# Qwiic_Power_Meter-ACS37800.net
KiCad netlist of a schematic drawn in EAGLE
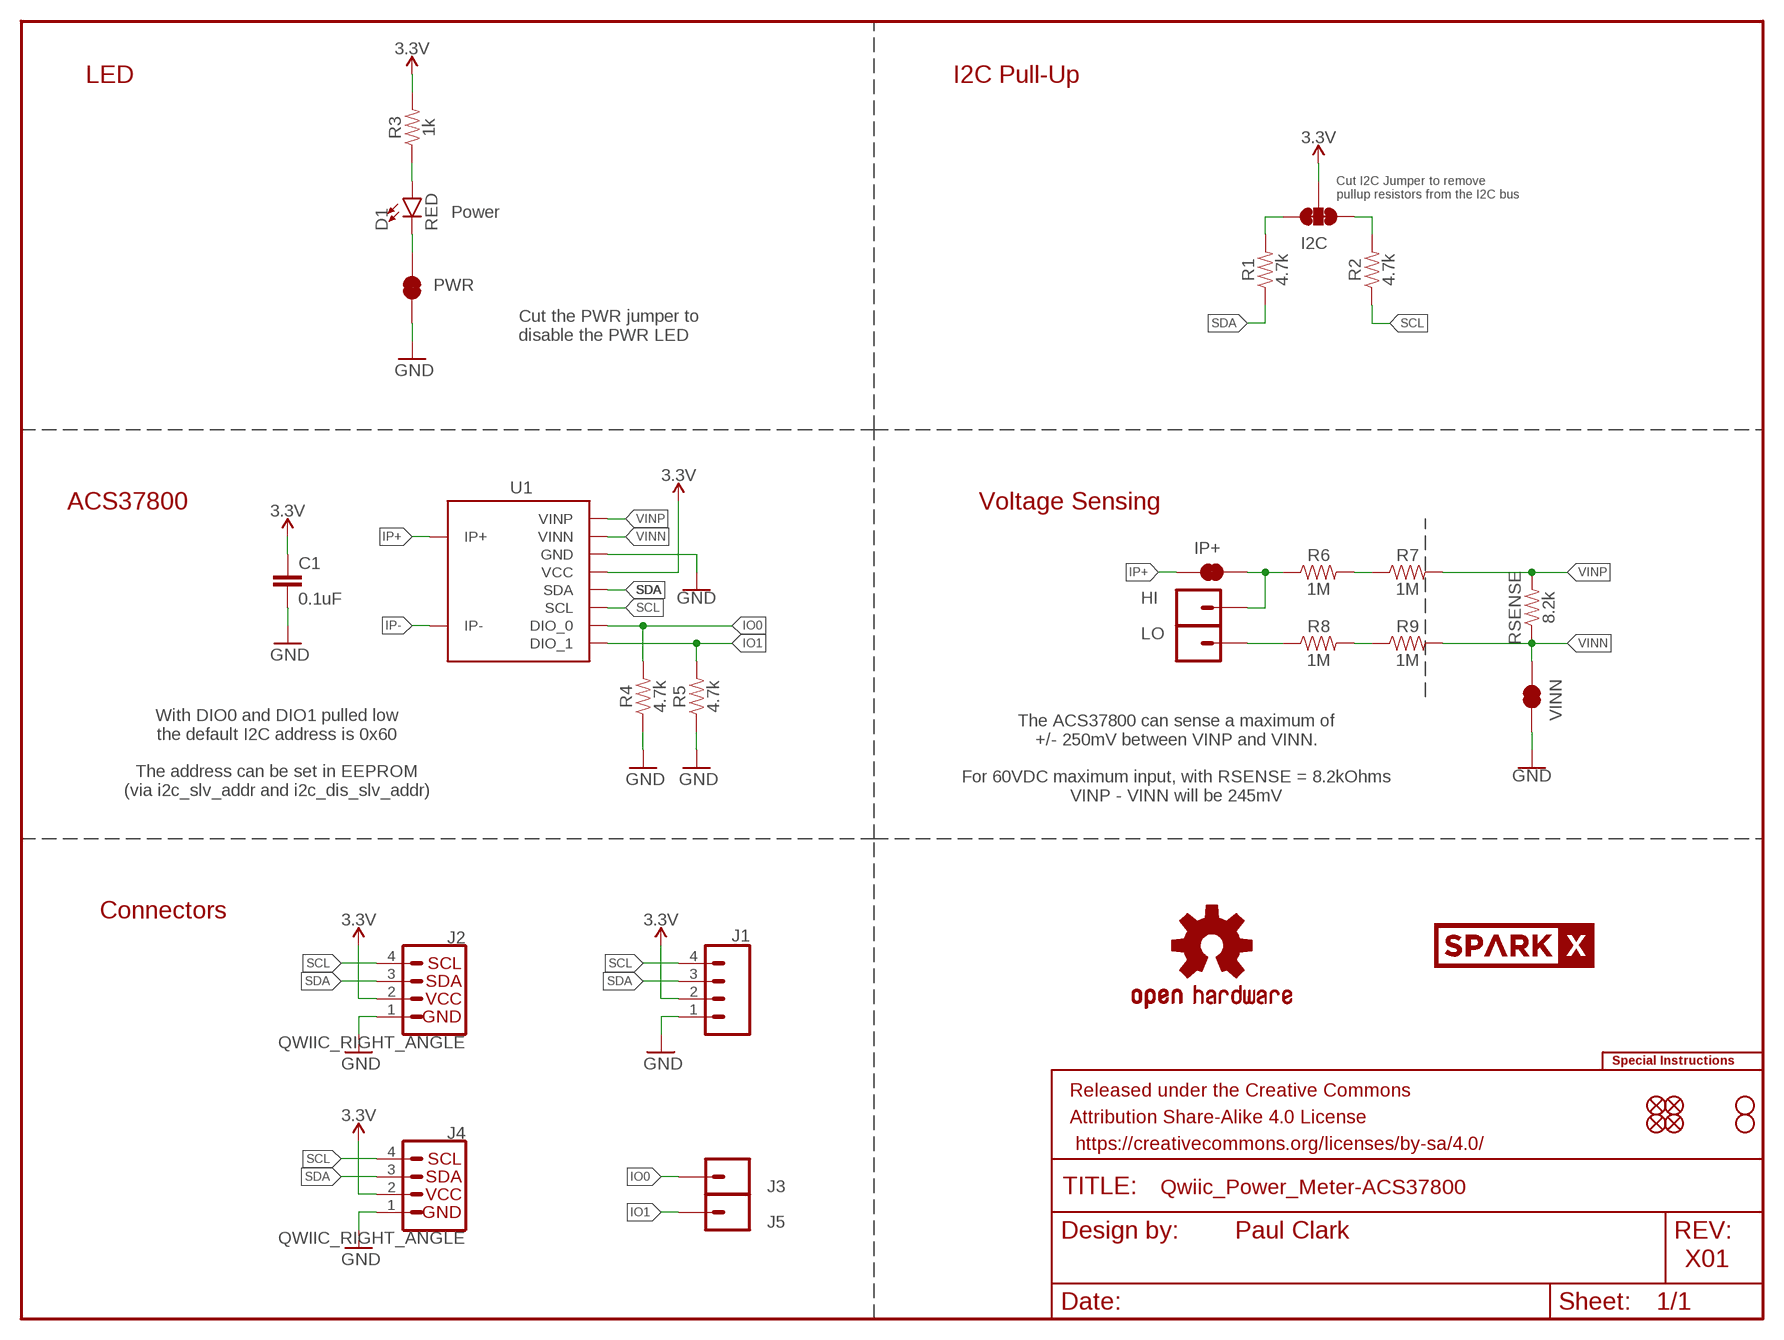
[diagram p0: schematic, sheet 1]

(export (version "E")
  (design (tool "Eeschema 10.0.6"))
  (components
    (comp (ref "C1")
      (value "0.1uF")
      (footprint "eagle-import:0603")
      (libsource (lib "eagle-import") (part "0.1UF-0603-25V-(+80/-20%)"))
    )
    (comp (ref "D1")
      (value "RED")
      (footprint "eagle-import:LED-0603")
      (libsource (lib "eagle-import") (part "LED-RED0603"))
    )
    (comp (ref "FRAME1")
      (value "FRAME-LETTER")
      (footprint "eagle-import:CREATIVE_COMMONS")
      (libsource (lib "eagle-import") (part "FRAME-LETTER"))
    )
    (comp (ref "HI")
      (value "CONN_01PTH_NO_SILK_YES_STOP")
      (footprint "eagle-import:1X01_NO_SILK")
      (libsource (lib "eagle-import") (part "CONN_01PTH_NO_SILK_YES_STOP"))
    )
    (comp (ref "I2C")
      (value "JUMPER-SMT_3_2-NC_TRACE_SILK")
      (footprint "eagle-import:SMT-JUMPER_3_2-NC_TRACE_SILK")
      (libsource (lib "eagle-import") (part "JUMPER-SMT_3_2-NC_TRACE_SILK"))
    )
    (comp (ref "IP+")
      (value "JUMPER-SMT_2_NC_TRACE_SILK")
      (footprint "eagle-import:SMT-JUMPER_2_NC_TRACE_SILK")
      (libsource (lib "eagle-import") (part "JUMPER-SMT_2_NC_TRACE_SILK"))
    )
    (comp (ref "J1")
      (value "CONN_041X04_NO_SILK")
      (footprint "eagle-import:1X04_NO_SILK")
      (libsource (lib "eagle-import") (part "CONN_041X04_NO_SILK"))
    )
    (comp (ref "J2")
      (value "QWIIC_RIGHT_ANGLE")
      (footprint "eagle-import:JST04_1MM_RA")
      (libsource (lib "eagle-import") (part "QWIIC_CONNECTORJS-1MM"))
    )
    (comp (ref "J3")
      (value "CONN_01PTH_NO_SILK_YES_STOP")
      (footprint "eagle-import:1X01_NO_SILK")
      (libsource (lib "eagle-import") (part "CONN_01PTH_NO_SILK_YES_STOP"))
    )
    (comp (ref "J4")
      (value "QWIIC_RIGHT_ANGLE")
      (footprint "eagle-import:JST04_1MM_RA")
      (libsource (lib "eagle-import") (part "QWIIC_CONNECTORJS-1MM"))
    )
    (comp (ref "J5")
      (value "CONN_01PTH_NO_SILK_YES_STOP")
      (footprint "eagle-import:1X01_NO_SILK")
      (libsource (lib "eagle-import") (part "CONN_01PTH_NO_SILK_YES_STOP"))
    )
    (comp (ref "JP1")
      (value "FIDUCIALUFIDUCIAL")
      (footprint "eagle-import:MICRO-FIDUCIAL")
      (libsource (lib "eagle-import") (part "FIDUCIALUFIDUCIAL"))
    )
    (comp (ref "JP2")
      (value "FIDUCIALUFIDUCIAL")
      (footprint "eagle-import:MICRO-FIDUCIAL")
      (libsource (lib "eagle-import") (part "FIDUCIALUFIDUCIAL"))
    )
    (comp (ref "JP3")
      (value "STAND-OFF")
      (footprint "eagle-import:STAND-OFF")
      (libsource (lib "eagle-import") (part "STAND-OFF"))
    )
    (comp (ref "JP4")
      (value "STAND-OFF")
      (footprint "eagle-import:STAND-OFF")
      (libsource (lib "eagle-import") (part "STAND-OFF"))
    )
    (comp (ref "JP5")
      (value "FIDUCIALUFIDUCIAL")
      (footprint "eagle-import:MICRO-FIDUCIAL")
      (libsource (lib "eagle-import") (part "FIDUCIALUFIDUCIAL"))
    )
    (comp (ref "JP6")
      (value "FIDUCIALUFIDUCIAL")
      (footprint "eagle-import:MICRO-FIDUCIAL")
      (libsource (lib "eagle-import") (part "FIDUCIALUFIDUCIAL"))
    )
    (comp (ref "LO")
      (value "CONN_01PTH_NO_SILK_YES_STOP")
      (footprint "eagle-import:1X01_NO_SILK")
      (libsource (lib "eagle-import") (part "CONN_01PTH_NO_SILK_YES_STOP"))
    )
    (comp (ref "LOGO1")
      (value "SPECIAL_INSTRUCTIONS-ORDERING")
      (footprint "eagle-import:ORDERING_INSTRUCTIONS")
      (libsource (lib "eagle-import") (part "SPECIAL_INSTRUCTIONS-ORDERING"))
    )
    (comp (ref "LOGO5")
      (value "OSHW-LOGOS")
      (footprint "eagle-import:OSHW-LOGO-S")
      (libsource (lib "eagle-import") (part "OSHW-LOGOS"))
    )
    (comp (ref "PWR")
      (value "JUMPER-SMT_2_NC_TRACE_SILK")
      (footprint "eagle-import:SMT-JUMPER_2_NC_TRACE_SILK")
      (libsource (lib "eagle-import") (part "JUMPER-SMT_2_NC_TRACE_SILK"))
    )
    (comp (ref "R1")
      (value "4.7k")
      (footprint "eagle-import:0603")
      (libsource (lib "eagle-import") (part "4.7KOHM-0603-1/10W-1%"))
    )
    (comp (ref "R2")
      (value "4.7k")
      (footprint "eagle-import:0603")
      (libsource (lib "eagle-import") (part "4.7KOHM-0603-1/10W-1%"))
    )
    (comp (ref "R3")
      (value "1k")
      (footprint "eagle-import:0603")
      (libsource (lib "eagle-import") (part "1KOHM-0603-1/10W-1%"))
    )
    (comp (ref "R4")
      (value "4.7k")
      (footprint "eagle-import:0603")
      (libsource (lib "eagle-import") (part "4.7KOHM-0603-1/10W-1%"))
    )
    (comp (ref "R5")
      (value "4.7k")
      (footprint "eagle-import:0603")
      (libsource (lib "eagle-import") (part "4.7KOHM-0603-1/10W-1%"))
    )
    (comp (ref "R6")
      (value "1M")
      (footprint "eagle-import:0603")
      (libsource (lib "eagle-import") (part "1MOHM-0603-1/4W-5%"))
    )
    (comp (ref "R7")
      (value "1M")
      (footprint "eagle-import:0603")
      (libsource (lib "eagle-import") (part "1MOHM-0603-1/4W-5%"))
    )
    (comp (ref "R8")
      (value "1M")
      (footprint "eagle-import:0603")
      (libsource (lib "eagle-import") (part "1MOHM-0603-1/4W-5%"))
    )
    (comp (ref "R9")
      (value "1M")
      (footprint "eagle-import:0603")
      (libsource (lib "eagle-import") (part "1MOHM-0603-1/4W-5%"))
    )
    (comp (ref "RSENSE")
      (value "8.2k")
      (footprint "eagle-import:0603")
      (libsource (lib "eagle-import") (part "8.2KOHM-0603-1/10W-5%"))
    )
    (comp (ref "U$18")
      (value "SPARKX-LOGO3")
      (footprint "eagle-import:SPARKX-SMALL")
      (libsource (lib "eagle-import") (part "SPARKX-LOGO3"))
    )
    (comp (ref "U1")
      (value "ACS37800")
      (footprint "eagle-import:ACS37800_THROUGH_HOLE")
      (fields
        (field (name "DIGIKEY_PART") "620-ACS37800KMACTR-030B3-I2CCT-ND")
        (field (name "MANU_PART") "ACS37800KMACTR-030B3-I2C")
      )
      (libsource (lib "eagle-import") (part "ACS37800"))
    )
    (comp (ref "VINN")
      (value "JUMPER-SMT_2_NC_TRACE_SILK")
      (footprint "eagle-import:SMT-JUMPER_2_NC_TRACE_SILK")
      (libsource (lib "eagle-import") (part "JUMPER-SMT_2_NC_TRACE_SILK"))
    )
  )
  (nets
    (net (code "1") (name "3.3V") (class "Default")
      (node (ref "C1") (pin "1") (pinfunction "1_1") (pintype "passive"))
      (node (ref "I2C") (pin "2") (pinfunction "2_2") (pintype "passive"))
      (node (ref "J1") (pin "2") (pinfunction "2_2") (pintype "passive"))
      (node (ref "J2") (pin "2") (pinfunction "2_2") (pintype "power_in"))
      (node (ref "J4") (pin "2") (pinfunction "2_2") (pintype "power_in"))
      (node (ref "R3") (pin "2") (pinfunction "2_2") (pintype "passive"))
      (node (ref "U1") (pin "13") (pinfunction "VCC_13") (pintype "power_in"))
    )
    (net (code "2") (name "GND") (class "Default")
      (node (ref "C1") (pin "2") (pinfunction "2_2") (pintype "passive"))
      (node (ref "J1") (pin "1") (pinfunction "1_1") (pintype "passive"))
      (node (ref "J2") (pin "1") (pinfunction "1_1") (pintype "power_in"))
      (node (ref "J4") (pin "1") (pinfunction "1_1") (pintype "power_in"))
      (node (ref "PWR") (pin "1") (pinfunction "1_1") (pintype "passive"))
      (node (ref "R4") (pin "1") (pinfunction "1_1") (pintype "passive"))
      (node (ref "R5") (pin "1") (pinfunction "1_1") (pintype "passive"))
      (node (ref "U1") (pin "14") (pinfunction "GND_14") (pintype "power_in"))
      (node (ref "VINN") (pin "2") (pinfunction "2_2") (pintype "passive"))
    )
    (net (code "3") (name "IO0") (class "Default")
      (node (ref "J3") (pin "1") (pinfunction "1_1") (pintype "passive"))
      (node (ref "R4") (pin "2") (pinfunction "2_2") (pintype "passive"))
      (node (ref "U1") (pin "10") (pinfunction "DIO_0_10") (pintype "bidirectional"))
    )
    (net (code "4") (name "IO1") (class "Default")
      (node (ref "J5") (pin "1") (pinfunction "1_1") (pintype "passive"))
      (node (ref "R5") (pin "2") (pinfunction "2_2") (pintype "passive"))
      (node (ref "U1") (pin "9") (pinfunction "DIO_1_9") (pintype "bidirectional"))
    )
    (net (code "5") (name "IP+") (class "Default")
      (node (ref "IP+") (pin "1") (pinfunction "1_1") (pintype "passive"))
      (node (ref "U1") (pin "1") (pinfunction "IP+_1") (pintype "bidirectional"))
      (node (ref "U1") (pin "2") (pinfunction "IP+_2") (pintype "bidirectional"))
      (node (ref "U1") (pin "3") (pinfunction "IP+_3") (pintype "bidirectional"))
      (node (ref "U1") (pin "4") (pinfunction "IP+_4") (pintype "bidirectional"))
      (node (ref "U1") (pin "CIN1") (pinfunction "IP+_CIN1") (pintype "bidirectional"))
      (node (ref "U1") (pin "CIN10") (pinfunction "IP+_CIN10") (pintype "bidirectional"))
      (node (ref "U1") (pin "CIN11") (pinfunction "IP+_CIN11") (pintype "bidirectional"))
      (node (ref "U1") (pin "CIN12") (pinfunction "IP+_CIN12") (pintype "bidirectional"))
      (node (ref "U1") (pin "CIN13") (pinfunction "IP+_CIN13") (pintype "bidirectional"))
      (node (ref "U1") (pin "CIN14") (pinfunction "IP+_CIN14") (pintype "bidirectional"))
      (node (ref "U1") (pin "CIN15") (pinfunction "IP+_CIN15") (pintype "bidirectional"))
      (node (ref "U1") (pin "CIN16") (pinfunction "IP+_CIN16") (pintype "bidirectional"))
      (node (ref "U1") (pin "CIN17") (pinfunction "IP+_CIN17") (pintype "bidirectional"))
      (node (ref "U1") (pin "CIN18") (pinfunction "IP+_CIN18") (pintype "bidirectional"))
      (node (ref "U1") (pin "CIN19") (pinfunction "IP+_CIN19") (pintype "bidirectional"))
      (node (ref "U1") (pin "CIN2") (pinfunction "IP+_CIN2") (pintype "bidirectional"))
      (node (ref "U1") (pin "CIN20") (pinfunction "IP+_CIN20") (pintype "bidirectional"))
      (node (ref "U1") (pin "CIN21") (pinfunction "IP+_CIN21") (pintype "bidirectional"))
      (node (ref "U1") (pin "CIN22") (pinfunction "IP+_CIN22") (pintype "bidirectional"))
      (node (ref "U1") (pin "CIN23") (pinfunction "IP+_CIN23") (pintype "bidirectional"))
      (node (ref "U1") (pin "CIN24") (pinfunction "IP+_CIN24") (pintype "bidirectional"))
      (node (ref "U1") (pin "CIN25") (pinfunction "IP+_CIN25") (pintype "bidirectional"))
      (node (ref "U1") (pin "CIN26") (pinfunction "IP+_CIN26") (pintype "bidirectional"))
      (node (ref "U1") (pin "CIN27") (pinfunction "IP+_CIN27") (pintype "bidirectional"))
      (node (ref "U1") (pin "CIN28") (pinfunction "IP+_CIN28") (pintype "bidirectional"))
      (node (ref "U1") (pin "CIN29") (pinfunction "IP+_CIN29") (pintype "bidirectional"))
      (node (ref "U1") (pin "CIN3") (pinfunction "IP+_CIN3") (pintype "bidirectional"))
      (node (ref "U1") (pin "CIN30") (pinfunction "IP+_CIN30") (pintype "bidirectional"))
      (node (ref "U1") (pin "CIN31") (pinfunction "IP+_CIN31") (pintype "bidirectional"))
      (node (ref "U1") (pin "CIN32") (pinfunction "IP+_CIN32") (pintype "bidirectional"))
      (node (ref "U1") (pin "CIN33") (pinfunction "IP+_CIN33") (pintype "bidirectional"))
      (node (ref "U1") (pin "CIN34") (pinfunction "IP+_CIN34") (pintype "bidirectional"))
      (node (ref "U1") (pin "CIN35") (pinfunction "IP+_CIN35") (pintype "bidirectional"))
      (node (ref "U1") (pin "CIN36") (pinfunction "IP+_CIN36") (pintype "bidirectional"))
      (node (ref "U1") (pin "CIN4") (pinfunction "IP+_CIN4") (pintype "bidirectional"))
      (node (ref "U1") (pin "CIN5") (pinfunction "IP+_CIN5") (pintype "bidirectional"))
      (node (ref "U1") (pin "CIN6") (pinfunction "IP+_CIN6") (pintype "bidirectional"))
      (node (ref "U1") (pin "CIN7") (pinfunction "IP+_CIN7") (pintype "bidirectional"))
      (node (ref "U1") (pin "CIN8") (pinfunction "IP+_CIN8") (pintype "bidirectional"))
      (node (ref "U1") (pin "CIN9") (pinfunction "IP+_CIN9") (pintype "bidirectional"))
      (node (ref "U1") (pin "C_IN") (pinfunction "IP+_C_IN") (pintype "bidirectional"))
      (node (ref "U1") (pin "C_IN_BREAKOUT") (pinfunction "IP+_C_IN_BREAKOUT") (pintype "bidirectional"))
    )
    (net (code "6") (name "IP-") (class "Default")
      (node (ref "U1") (pin "5") (pinfunction "IP-_5") (pintype "bidirectional"))
      (node (ref "U1") (pin "6") (pinfunction "IP-_6") (pintype "bidirectional"))
      (node (ref "U1") (pin "7") (pinfunction "IP-_7") (pintype "bidirectional"))
      (node (ref "U1") (pin "8") (pinfunction "IP-_8") (pintype "bidirectional"))
      (node (ref "U1") (pin "COUT1") (pinfunction "IP-_COUT1") (pintype "bidirectional"))
      (node (ref "U1") (pin "COUT10") (pinfunction "IP-_COUT10") (pintype "bidirectional"))
      (node (ref "U1") (pin "COUT11") (pinfunction "IP-_COUT11") (pintype "bidirectional"))
      (node (ref "U1") (pin "COUT12") (pinfunction "IP-_COUT12") (pintype "bidirectional"))
      (node (ref "U1") (pin "COUT13") (pinfunction "IP-_COUT13") (pintype "bidirectional"))
      (node (ref "U1") (pin "COUT14") (pinfunction "IP-_COUT14") (pintype "bidirectional"))
      (node (ref "U1") (pin "COUT15") (pinfunction "IP-_COUT15") (pintype "bidirectional"))
      (node (ref "U1") (pin "COUT16") (pinfunction "IP-_COUT16") (pintype "bidirectional"))
      (node (ref "U1") (pin "COUT17") (pinfunction "IP-_COUT17") (pintype "bidirectional"))
      (node (ref "U1") (pin "COUT18") (pinfunction "IP-_COUT18") (pintype "bidirectional"))
      (node (ref "U1") (pin "COUT19") (pinfunction "IP-_COUT19") (pintype "bidirectional"))
      (node (ref "U1") (pin "COUT2") (pinfunction "IP-_COUT2") (pintype "bidirectional"))
      (node (ref "U1") (pin "COUT20") (pinfunction "IP-_COUT20") (pintype "bidirectional"))
      (node (ref "U1") (pin "COUT21") (pinfunction "IP-_COUT21") (pintype "bidirectional"))
      (node (ref "U1") (pin "COUT22") (pinfunction "IP-_COUT22") (pintype "bidirectional"))
      (node (ref "U1") (pin "COUT23") (pinfunction "IP-_COUT23") (pintype "bidirectional"))
      (node (ref "U1") (pin "COUT24") (pinfunction "IP-_COUT24") (pintype "bidirectional"))
      (node (ref "U1") (pin "COUT25") (pinfunction "IP-_COUT25") (pintype "bidirectional"))
      (node (ref "U1") (pin "COUT26") (pinfunction "IP-_COUT26") (pintype "bidirectional"))
      (node (ref "U1") (pin "COUT27") (pinfunction "IP-_COUT27") (pintype "bidirectional"))
      (node (ref "U1") (pin "COUT28") (pinfunction "IP-_COUT28") (pintype "bidirectional"))
      (node (ref "U1") (pin "COUT29") (pinfunction "IP-_COUT29") (pintype "bidirectional"))
      (node (ref "U1") (pin "COUT3") (pinfunction "IP-_COUT3") (pintype "bidirectional"))
      (node (ref "U1") (pin "COUT30") (pinfunction "IP-_COUT30") (pintype "bidirectional"))
      (node (ref "U1") (pin "COUT31") (pinfunction "IP-_COUT31") (pintype "bidirectional"))
      (node (ref "U1") (pin "COUT32") (pinfunction "IP-_COUT32") (pintype "bidirectional"))
      (node (ref "U1") (pin "COUT33") (pinfunction "IP-_COUT33") (pintype "bidirectional"))
      (node (ref "U1") (pin "COUT34") (pinfunction "IP-_COUT34") (pintype "bidirectional"))
      (node (ref "U1") (pin "COUT35") (pinfunction "IP-_COUT35") (pintype "bidirectional"))
      (node (ref "U1") (pin "COUT36") (pinfunction "IP-_COUT36") (pintype "bidirectional"))
      (node (ref "U1") (pin "COUT4") (pinfunction "IP-_COUT4") (pintype "bidirectional"))
      (node (ref "U1") (pin "COUT5") (pinfunction "IP-_COUT5") (pintype "bidirectional"))
      (node (ref "U1") (pin "COUT6") (pinfunction "IP-_COUT6") (pintype "bidirectional"))
      (node (ref "U1") (pin "COUT7") (pinfunction "IP-_COUT7") (pintype "bidirectional"))
      (node (ref "U1") (pin "COUT8") (pinfunction "IP-_COUT8") (pintype "bidirectional"))
      (node (ref "U1") (pin "COUT9") (pinfunction "IP-_COUT9") (pintype "bidirectional"))
      (node (ref "U1") (pin "C_OUT") (pinfunction "IP-_C_OUT") (pintype "bidirectional"))
      (node (ref "U1") (pin "C_OUT_BREAKOUT") (pinfunction "IP-_C_OUT_BREAKOUT") (pintype "bidirectional"))
    )
    (net (code "7") (name "Net-(D1-PadA)") (class "Default")
      (node (ref "D1") (pin "A") (pinfunction "A_A") (pintype "passive"))
      (node (ref "R3") (pin "1") (pinfunction "1_1") (pintype "passive"))
    )
    (net (code "8") (name "Net-(D1-PadC)") (class "Default")
      (node (ref "D1") (pin "C") (pinfunction "C_C") (pintype "passive"))
      (node (ref "PWR") (pin "2") (pinfunction "2_2") (pintype "passive"))
    )
    (net (code "9") (name "Net-(HI-Pad1)") (class "Default")
      (node (ref "HI") (pin "1") (pinfunction "1_1") (pintype "passive"))
      (node (ref "IP+") (pin "2") (pinfunction "2_2") (pintype "passive"))
      (node (ref "R6") (pin "1") (pinfunction "1_1") (pintype "passive"))
    )
    (net (code "10") (name "Net-(I2C-Pad1)") (class "Default")
      (node (ref "I2C") (pin "1") (pinfunction "1_1") (pintype "passive"))
      (node (ref "R2") (pin "2") (pinfunction "2_2") (pintype "passive"))
    )
    (net (code "11") (name "Net-(I2C-Pad3)") (class "Default")
      (node (ref "I2C") (pin "3") (pinfunction "3_3") (pintype "passive"))
      (node (ref "R1") (pin "2") (pinfunction "2_2") (pintype "passive"))
    )
    (net (code "12") (name "Net-(LO-Pad1)") (class "Default")
      (node (ref "LO") (pin "1") (pinfunction "1_1") (pintype "passive"))
      (node (ref "R8") (pin "1") (pinfunction "1_1") (pintype "passive"))
    )
    (net (code "13") (name "Net-(R6-Pad2)") (class "Default")
      (node (ref "R6") (pin "2") (pinfunction "2_2") (pintype "passive"))
      (node (ref "R7") (pin "1") (pinfunction "1_1") (pintype "passive"))
    )
    (net (code "14") (name "Net-(R8-Pad2)") (class "Default")
      (node (ref "R8") (pin "2") (pinfunction "2_2") (pintype "passive"))
      (node (ref "R9") (pin "1") (pinfunction "1_1") (pintype "passive"))
    )
    (net (code "15") (name "SCL") (class "Default")
      (node (ref "J1") (pin "4") (pinfunction "4_4") (pintype "passive"))
      (node (ref "J2") (pin "4") (pinfunction "4_4") (pintype "passive"))
      (node (ref "J4") (pin "4") (pinfunction "4_4") (pintype "passive"))
      (node (ref "R2") (pin "1") (pinfunction "1_1") (pintype "passive"))
      (node (ref "U1") (pin "11") (pinfunction "SCL_11") (pintype "bidirectional"))
    )
    (net (code "16") (name "SDA") (class "Default")
      (node (ref "J1") (pin "3") (pinfunction "3_3") (pintype "passive"))
      (node (ref "J2") (pin "3") (pinfunction "3_3") (pintype "passive"))
      (node (ref "J4") (pin "3") (pinfunction "3_3") (pintype "passive"))
      (node (ref "R1") (pin "1") (pinfunction "1_1") (pintype "passive"))
      (node (ref "U1") (pin "12") (pinfunction "SDA_12") (pintype "bidirectional"))
    )
    (net (code "17") (name "VINN") (class "Default")
      (node (ref "R9") (pin "2") (pinfunction "2_2") (pintype "passive"))
      (node (ref "RSENSE") (pin "1") (pinfunction "1_1") (pintype "passive"))
      (node (ref "U1") (pin "15") (pinfunction "VINN_15") (pintype "power_in"))
      (node (ref "VINN") (pin "1") (pinfunction "1_1") (pintype "passive"))
    )
    (net (code "18") (name "VINP") (class "Default")
      (node (ref "R7") (pin "2") (pinfunction "2_2") (pintype "passive"))
      (node (ref "RSENSE") (pin "2") (pinfunction "2_2") (pintype "passive"))
      (node (ref "U1") (pin "16") (pinfunction "VINP_16") (pintype "power_in"))
    )
  )
)
